# OneDollarBoard_com_1_004_r1.net
KiCad netlist of a schematic drawn in EAGLE
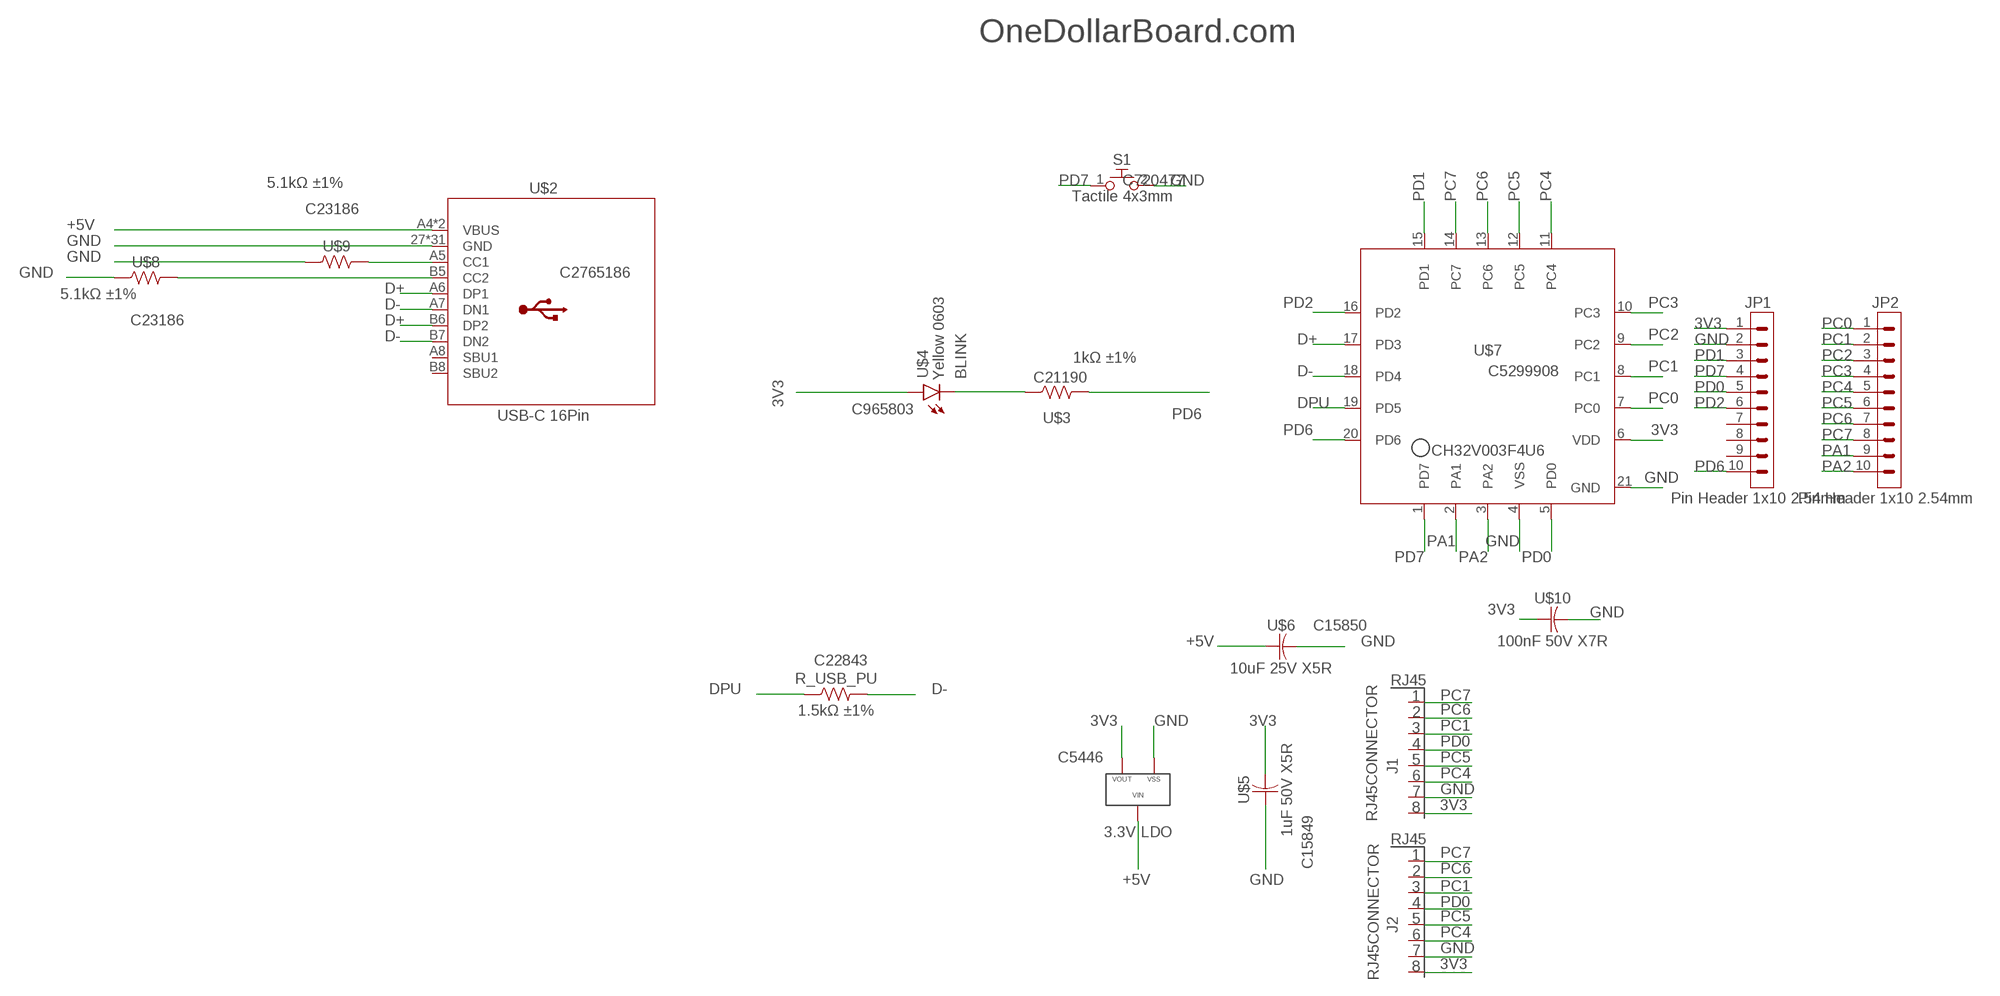
[diagram p0: schematic, sheet 1]

(export (version "E")
  (design (tool "Eeschema 10.0.6"))
  (components
    (comp (ref "J1")
      (value "RJ45CONNECTOR")
      (footprint "eagle-import:2.54_1.0")
      (libsource (lib "eagle-import") (part "RJ45CONNECTOR"))
    )
    (comp (ref "J2")
      (value "RJ45CONNECTOR")
      (footprint "eagle-import:2.54_1.0")
      (libsource (lib "eagle-import") (part "RJ45CONNECTOR"))
    )
    (comp (ref "JP1")
      (value "Pin Header 1x10 2.54mm")
      (footprint "eagle-import:1X10")
      (fields
        (field (name "LCSC_PART") "C350306")
        (field (name "MANUFACTURER") "HOAUC")
        (field (name "MFR_PART") "2685Y-110CNG1SNA01")
      )
      (libsource (lib "eagle-import") (part "PINHD-1X10"))
    )
    (comp (ref "JP2")
      (value "Pin Header 1x10 2.54mm")
      (footprint "eagle-import:1X10")
      (fields
        (field (name "LCSC_PART") "C350306")
        (field (name "MANUFACTURER") "HOAUC")
        (field (name "MFR_PART") "2685Y-110CNG1SNA01")
      )
      (libsource (lib "eagle-import") (part "PINHD-1X10"))
    )
    (comp (ref "R_USB_PU")
      (value "1.5kΩ ±1%")
      (footprint "eagle-import:WRIS-RSKS_0603_WAVE")
      (fields
        (field (name "LCSC_PART") "C22843")
        (field (name "MANUFACTURER") "UNI-ROYAL")
        (field (name "MFR_PART") "0603WAF1501T5E")
        (field (name "LCSC") "C22843")
      )
      (libsource (lib "eagle-import") (part "R_0603_1.5K"))
    )
    (comp (ref "S1")
      (value "Tactile 4x3mm")
      (footprint "eagle-import:B3U-1000P(M)")
      (fields
        (field (name "LCSC_PART") "C720477")
        (field (name "MANUFACTURER") "XUNPU")
        (field (name "MFR_PART") "TS-1088-AR02016")
        (field (name "LCSC") "C720477")
      )
      (libsource (lib "eagle-import") (part "B3U-X0001000P(M)B3U-1000P(M)"))
    )
    (comp (ref "U$1")
      (value "3.3V LDO")
      (footprint "eagle-import:XC6206P332MR-G")
      (fields
        (field (name "LCSC_PART") "C5446")
        (field (name "MANUFACTURER") "TOREX")
        (field (name "MFR_PART") "XC6206P332MR-G")
        (field (name "LCSC") "C5446")
      )
      (libsource (lib "eagle-import") (part "XC6206P332MR-G"))
    )
    (comp (ref "U$2")
      (value "USB-C 16Pin")
      (footprint "eagle-import:CONN_TYPE-C-16P")
      (fields
        (field (name "LCSC_PART") "C2765186")
        (field (name "MANUFACTURER") "SHOU HAN")
        (field (name "MFR_PART") "TYPE-C_16PIN_2MD(073)")
        (field (name "LCSC") "C2765186")
      )
      (libsource (lib "eagle-import") (part "USB-C"))
    )
    (comp (ref "U$3")
      (value "1kΩ ±1%")
      (footprint "eagle-import:RESC2208X45")
      (fields
        (field (name "LCSC_PART") "C21190")
        (field (name "MANUFACTURER") "UNI-ROYAL")
        (field (name "MFR_PART") "0603WAF1001T5E")
        (field (name "LCSC") "C21190")
      )
      (libsource (lib "eagle-import") (part "R_0603_1K_1%_0.1W_C21190"))
    )
    (comp (ref "U$4")
      (value "Yellow 0603")
      (footprint "eagle-import:LEDC1507X40")
      (fields
        (field (name "LCSC_PART") "C965803")
        (field (name "MANUFACTURER") "XINGLIGHT")
        (field (name "MFR_PART") "XL-1608UYC-04")
        (field (name "LCSC") "C965803")
      )
      (libsource (lib "eagle-import") (part "LED"))
    )
    (comp (ref "U$5")
      (value "1uF 50V X5R")
      (footprint "eagle-import:CPA1UF")
      (fields
        (field (name "LCSC_PART") "C15849")
        (field (name "MANUFACTURER") "Samsung Electro-Mechanics")
        (field (name "MFR_PART") "CL10A105KB8NNNC")
        (field (name "LCSC") "C15849")
      )
      (libsource (lib "eagle-import") (part "CAP1UF"))
    )
    (comp (ref "U$6")
      (value "10uF 25V X5R")
      (footprint "eagle-import:CAP0603")
      (fields
        (field (name "LCSC_PART") "C15850")
        (field (name "MANUFACTURER") "Samsung Electro-Mechanics")
        (field (name "MFR_PART") "CL21A106KAYNNNE")
        (field (name "LCSC") "C15850")
      )
      (libsource (lib "eagle-import") (part "CAP10UF"))
    )
    (comp (ref "U$7")
      (value "CH32V003F4U6")
      (footprint "eagle-import:CH32V003F4U6")
      (fields
        (field (name "LCSC_PART") "C5299908")
        (field (name "MANUFACTURER") "WCH")
        (field (name "LCSC") "C5299908")
      )
      (libsource (lib "eagle-import") (part "CH32V003"))
    )
    (comp (ref "U$8")
      (value "5.1kΩ ±1%")
      (footprint "eagle-import:WRIS-RSKS_0603_REFLOW")
      (fields
        (field (name "LCSC_PART") "C23186")
        (field (name "MANUFACTURER") "UNI-ROYAL")
        (field (name "MFR_PART") "0603WAF5101T5E")
        (field (name "LCSC") "C23186")
      )
      (libsource (lib "eagle-import") (part "R_0603_5.1KRES_0603"))
    )
    (comp (ref "U$9")
      (value "5.1kΩ ±1%")
      (footprint "eagle-import:WRIS-RSKS_0603_REFLOW")
      (fields
        (field (name "LCSC_PART") "C23186")
        (field (name "MANUFACTURER") "UNI-ROYAL")
        (field (name "MFR_PART") "0603WAF5101T5E")
        (field (name "LCSC") "C23186")
      )
      (libsource (lib "eagle-import") (part "R_0603_5.1KRES_0603"))
    )
    (comp (ref "U$10")
      (value "100nF 50V X7R")
      (footprint "eagle-import:CAP0603")
      (fields
        (field (name "LCSC_PART") "C30926")
        (field (name "MANUFACTURER") "FH")
        (field (name "MFR_PART") "0603B104K500NT")
      )
      (libsource (lib "eagle-import") (part "CAP100NF"))
    )
  )
  (nets
    (net (code "1") (name "/+5V") (class "Default")
      (node (ref "U$1") (pin "3") (pinfunction "3_3") (pintype "power_in"))
      (node (ref "U$2") (pin "A4") (pinfunction "VBUS_A4") (pintype "power_in"))
      (node (ref "U$2") (pin "B4") (pinfunction "VBUS_B4") (pintype "power_in"))
      (node (ref "U$6") (pin "1") (pinfunction "1_1") (pintype "passive"))
    )
    (net (code "2") (name "/3V3") (class "Default")
      (node (ref "J1") (pin "P$1") (pinfunction "P1_P$1") (pintype "passive"))
      (node (ref "J2") (pin "P$1") (pinfunction "P1_P$1") (pintype "passive"))
      (node (ref "JP1") (pin "1") (pinfunction "1_1") (pintype "passive"))
      (node (ref "U$1") (pin "2") (pinfunction "2_2") (pintype "power_in"))
      (node (ref "U$10") (pin "1") (pinfunction "1_1") (pintype "passive"))
      (node (ref "U$4") (pin "A") (pinfunction "A_A") (pintype "passive"))
      (node (ref "U$5") (pin "2") (pinfunction "2_2") (pintype "passive"))
      (node (ref "U$7") (pin "6") (pinfunction "VDD_6") (pintype "bidirectional"))
    )
    (net (code "3") (name "/BLINK") (class "Default")
      (node (ref "U$3") (pin "1") (pinfunction "1_1") (pintype "passive"))
      (node (ref "U$4") (pin "C") (pinfunction "C_C") (pintype "passive"))
    )
    (net (code "4") (name "/D+") (class "Default")
      (node (ref "U$2") (pin "A6") (pinfunction "DP1_A6") (pintype "bidirectional"))
      (node (ref "U$2") (pin "B6") (pinfunction "DP2_B6") (pintype "bidirectional"))
      (node (ref "U$7") (pin "17") (pinfunction "PD3_17") (pintype "bidirectional"))
    )
    (net (code "5") (name "/D-") (class "Default")
      (node (ref "R_USB_PU") (pin "2") (pinfunction "2_2") (pintype "passive"))
      (node (ref "U$2") (pin "A7") (pinfunction "DN1_A7") (pintype "bidirectional"))
      (node (ref "U$2") (pin "B7") (pinfunction "DN2_B7") (pintype "bidirectional"))
      (node (ref "U$7") (pin "18") (pinfunction "PD4_18") (pintype "bidirectional"))
    )
    (net (code "6") (name "/DPU") (class "Default")
      (node (ref "R_USB_PU") (pin "1") (pinfunction "1_1") (pintype "passive"))
      (node (ref "U$7") (pin "19") (pinfunction "PD5_19") (pintype "power_in"))
    )
    (net (code "7") (name "/GND") (class "Default")
      (node (ref "J1") (pin "P$2") (pinfunction "P2_P$2") (pintype "passive"))
      (node (ref "J2") (pin "P$2") (pinfunction "P2_P$2") (pintype "passive"))
      (node (ref "JP1") (pin "2") (pinfunction "2_2") (pintype "passive"))
      (node (ref "S1") (pin "2") (pinfunction "2_2") (pintype "passive"))
      (node (ref "U$1") (pin "1") (pinfunction "1_1") (pintype "power_in"))
      (node (ref "U$10") (pin "2") (pinfunction "2_2") (pintype "passive"))
      (node (ref "U$2") (pin "27") (pinfunction "GND_27") (pintype "power_in"))
      (node (ref "U$2") (pin "28") (pinfunction "GND_28") (pintype "power_in"))
      (node (ref "U$2") (pin "29") (pinfunction "GND_29") (pintype "power_in"))
      (node (ref "U$2") (pin "30") (pinfunction "GND_30") (pintype "power_in"))
      (node (ref "U$2") (pin "A1") (pinfunction "GND_A1") (pintype "power_in"))
      (node (ref "U$2") (pin "B1") (pinfunction "GND_B1") (pintype "power_in"))
      (node (ref "U$2") (pin "S_1") (pinfunction "GND_S_1") (pintype "power_in"))
      (node (ref "U$2") (pin "S_1_H1") (pinfunction "GND_S_1_H1") (pintype "power_in"))
      (node (ref "U$2") (pin "S_1_H2") (pinfunction "GND_S_1_H2") (pintype "power_in"))
      (node (ref "U$2") (pin "S_2") (pinfunction "GND_S_2") (pintype "power_in"))
      (node (ref "U$2") (pin "S_2_H1") (pinfunction "GND_S_2_H1") (pintype "power_in"))
      (node (ref "U$2") (pin "S_2_H12") (pinfunction "GND_S_2_H12") (pintype "power_in"))
      (node (ref "U$2") (pin "S_2_H13") (pinfunction "GND_S_2_H13") (pintype "power_in"))
      (node (ref "U$2") (pin "S_2_H2") (pinfunction "GND_S_2_H2") (pintype "power_in"))
      (node (ref "U$2") (pin "S_2_H3") (pinfunction "GND_S_2_H3") (pintype "power_in"))
      (node (ref "U$2") (pin "S_2_H4") (pinfunction "GND_S_2_H4") (pintype "power_in"))
      (node (ref "U$2") (pin "S_2_H5") (pinfunction "GND_S_2_H5") (pintype "power_in"))
      (node (ref "U$2") (pin "S_2_H6") (pinfunction "GND_S_2_H6") (pintype "power_in"))
      (node (ref "U$2") (pin "S_2_H7") (pinfunction "GND_S_2_H7") (pintype "power_in"))
      (node (ref "U$2") (pin "S_3") (pinfunction "GND_S_3") (pintype "power_in"))
      (node (ref "U$2") (pin "S_3_H1") (pinfunction "GND_S_3_H1") (pintype "power_in"))
      (node (ref "U$2") (pin "S_3_H2") (pinfunction "GND_S_3_H2") (pintype "power_in"))
      (node (ref "U$2") (pin "S_3_H3") (pinfunction "GND_S_3_H3") (pintype "power_in"))
      (node (ref "U$2") (pin "S_3_H4") (pinfunction "GND_S_3_H4") (pintype "power_in"))
      (node (ref "U$2") (pin "S_3_H5") (pinfunction "GND_S_3_H5") (pintype "power_in"))
      (node (ref "U$2") (pin "S_4") (pinfunction "GND_S_4") (pintype "power_in"))
      (node (ref "U$2") (pin "S_4_H1") (pinfunction "GND_S_4_H1") (pintype "power_in"))
      (node (ref "U$2") (pin "S_4_H2") (pinfunction "GND_S_4_H2") (pintype "power_in"))
      (node (ref "U$2") (pin "S_4_H3") (pinfunction "GND_S_4_H3") (pintype "power_in"))
      (node (ref "U$2") (pin "S_4_H4") (pinfunction "GND_S_4_H4") (pintype "power_in"))
      (node (ref "U$2") (pin "S_4_H5") (pinfunction "GND_S_4_H5") (pintype "power_in"))
      (node (ref "U$5") (pin "1") (pinfunction "1_1") (pintype "passive"))
      (node (ref "U$6") (pin "2") (pinfunction "2_2") (pintype "passive"))
      (node (ref "U$7") (pin "21") (pinfunction "GND_21") (pintype "bidirectional"))
      (node (ref "U$7") (pin "4") (pinfunction "VSS_4") (pintype "bidirectional"))
      (node (ref "U$8") (pin "1") (pinfunction "1_1") (pintype "passive"))
      (node (ref "U$9") (pin "1") (pinfunction "1_1") (pintype "passive"))
    )
    (net (code "8") (name "/PA1") (class "Default")
      (node (ref "JP2") (pin "9") (pinfunction "9_9") (pintype "passive"))
      (node (ref "U$7") (pin "2") (pinfunction "PA1_2") (pintype "bidirectional"))
    )
    (net (code "9") (name "/PA2") (class "Default")
      (node (ref "JP2") (pin "10") (pinfunction "10_10") (pintype "passive"))
      (node (ref "U$7") (pin "3") (pinfunction "PA2_3") (pintype "bidirectional"))
    )
    (net (code "10") (name "/PC0") (class "Default")
      (node (ref "JP2") (pin "1") (pinfunction "1_1") (pintype "passive"))
      (node (ref "U$7") (pin "7") (pinfunction "PC0_7") (pintype "bidirectional"))
    )
    (net (code "11") (name "/PC1") (class "Default")
      (node (ref "J1") (pin "P$6") (pinfunction "P6_P$6") (pintype "passive"))
      (node (ref "J2") (pin "P$6") (pinfunction "P6_P$6") (pintype "passive"))
      (node (ref "JP2") (pin "2") (pinfunction "2_2") (pintype "passive"))
      (node (ref "U$7") (pin "8") (pinfunction "PC1_8") (pintype "bidirectional"))
    )
    (net (code "12") (name "/PC2") (class "Default")
      (node (ref "JP2") (pin "3") (pinfunction "3_3") (pintype "passive"))
      (node (ref "U$7") (pin "9") (pinfunction "PC2_9") (pintype "bidirectional"))
    )
    (net (code "13") (name "/PC3") (class "Default")
      (node (ref "JP2") (pin "4") (pinfunction "4_4") (pintype "passive"))
      (node (ref "U$7") (pin "10") (pinfunction "PC3_10") (pintype "bidirectional"))
    )
    (net (code "14") (name "/PC4") (class "Default")
      (node (ref "J1") (pin "P$3") (pinfunction "P3_P$3") (pintype "passive"))
      (node (ref "J2") (pin "P$3") (pinfunction "P3_P$3") (pintype "passive"))
      (node (ref "JP2") (pin "5") (pinfunction "5_5") (pintype "passive"))
      (node (ref "U$7") (pin "11") (pinfunction "PC4_11") (pintype "bidirectional"))
    )
    (net (code "15") (name "/PC5") (class "Default")
      (node (ref "J1") (pin "P$4") (pinfunction "P4_P$4") (pintype "passive"))
      (node (ref "J2") (pin "P$4") (pinfunction "P4_P$4") (pintype "passive"))
      (node (ref "JP2") (pin "6") (pinfunction "6_6") (pintype "passive"))
      (node (ref "U$7") (pin "12") (pinfunction "PC5_12") (pintype "bidirectional"))
    )
    (net (code "16") (name "/PC6") (class "Default")
      (node (ref "J1") (pin "P$7") (pinfunction "P7_P$7") (pintype "passive"))
      (node (ref "J2") (pin "P$7") (pinfunction "P7_P$7") (pintype "passive"))
      (node (ref "JP2") (pin "7") (pinfunction "7_7") (pintype "passive"))
      (node (ref "U$7") (pin "13") (pinfunction "PC6_13") (pintype "bidirectional"))
    )
    (net (code "17") (name "/PC7") (class "Default")
      (node (ref "J1") (pin "P$8") (pinfunction "P8_P$8") (pintype "passive"))
      (node (ref "J2") (pin "P$8") (pinfunction "P8_P$8") (pintype "passive"))
      (node (ref "JP2") (pin "8") (pinfunction "8_8") (pintype "passive"))
      (node (ref "U$7") (pin "14") (pinfunction "PC7_14") (pintype "bidirectional"))
    )
    (net (code "18") (name "/PD0") (class "Default")
      (node (ref "J1") (pin "P$5") (pinfunction "P5_P$5") (pintype "passive"))
      (node (ref "J2") (pin "P$5") (pinfunction "P5_P$5") (pintype "passive"))
      (node (ref "JP1") (pin "5") (pinfunction "5_5") (pintype "passive"))
      (node (ref "U$7") (pin "5") (pinfunction "PD0_5") (pintype "bidirectional"))
    )
    (net (code "19") (name "/PD1") (class "Default")
      (node (ref "JP1") (pin "3") (pinfunction "3_3") (pintype "passive"))
      (node (ref "U$7") (pin "15") (pinfunction "PD1_15") (pintype "bidirectional"))
    )
    (net (code "20") (name "/PD2") (class "Default")
      (node (ref "JP1") (pin "6") (pinfunction "6_6") (pintype "passive"))
      (node (ref "U$7") (pin "16") (pinfunction "PD2_16") (pintype "bidirectional"))
    )
    (net (code "21") (name "/PD6") (class "Default")
      (node (ref "JP1") (pin "10") (pinfunction "10_10") (pintype "passive"))
      (node (ref "U$3") (pin "2") (pinfunction "2_2") (pintype "passive"))
      (node (ref "U$7") (pin "20") (pinfunction "PD6_20") (pintype "bidirectional"))
    )
    (net (code "22") (name "/PD7") (class "Default")
      (node (ref "JP1") (pin "4") (pinfunction "4_4") (pintype "passive"))
      (node (ref "S1") (pin "1") (pinfunction "1_1") (pintype "passive"))
      (node (ref "U$7") (pin "1") (pinfunction "PD7_1") (pintype "bidirectional"))
    )
    (net (code "23") (name "Net-(U$2-CC1)") (class "Default")
      (node (ref "U$2") (pin "A5") (pinfunction "CC1_A5") (pintype "bidirectional"))
      (node (ref "U$9") (pin "2") (pinfunction "2_2") (pintype "passive"))
    )
    (net (code "24") (name "Net-(U$2-CC2)") (class "Default")
      (node (ref "U$2") (pin "B5") (pinfunction "CC2_B5") (pintype "bidirectional"))
      (node (ref "U$8") (pin "2") (pinfunction "2_2") (pintype "passive"))
    )
    (net (code "25") (name "unconnected-(JP1-Pad7)") (class "Default")
      (node (ref "JP1") (pin "7") (pinfunction "7_7") (pintype "passive"))
    )
    (net (code "26") (name "unconnected-(JP1-Pad8)") (class "Default")
      (node (ref "JP1") (pin "8") (pinfunction "8_8") (pintype "passive"))
    )
    (net (code "27") (name "unconnected-(JP1-Pad9)") (class "Default")
      (node (ref "JP1") (pin "9") (pinfunction "9_9") (pintype "passive"))
    )
    (net (code "28") (name "unconnected-(U$2-SBU1-PadA8)") (class "Default")
      (node (ref "U$2") (pin "A8") (pinfunction "SBU1_A8") (pintype "bidirectional"))
    )
    (net (code "29") (name "unconnected-(U$2-SBU2-PadB8)") (class "Default")
      (node (ref "U$2") (pin "B8") (pinfunction "SBU2_B8") (pintype "bidirectional"))
    )
  )
)
